# BUS.net
KiCad netlist of a schematic drawn in Altium Designer
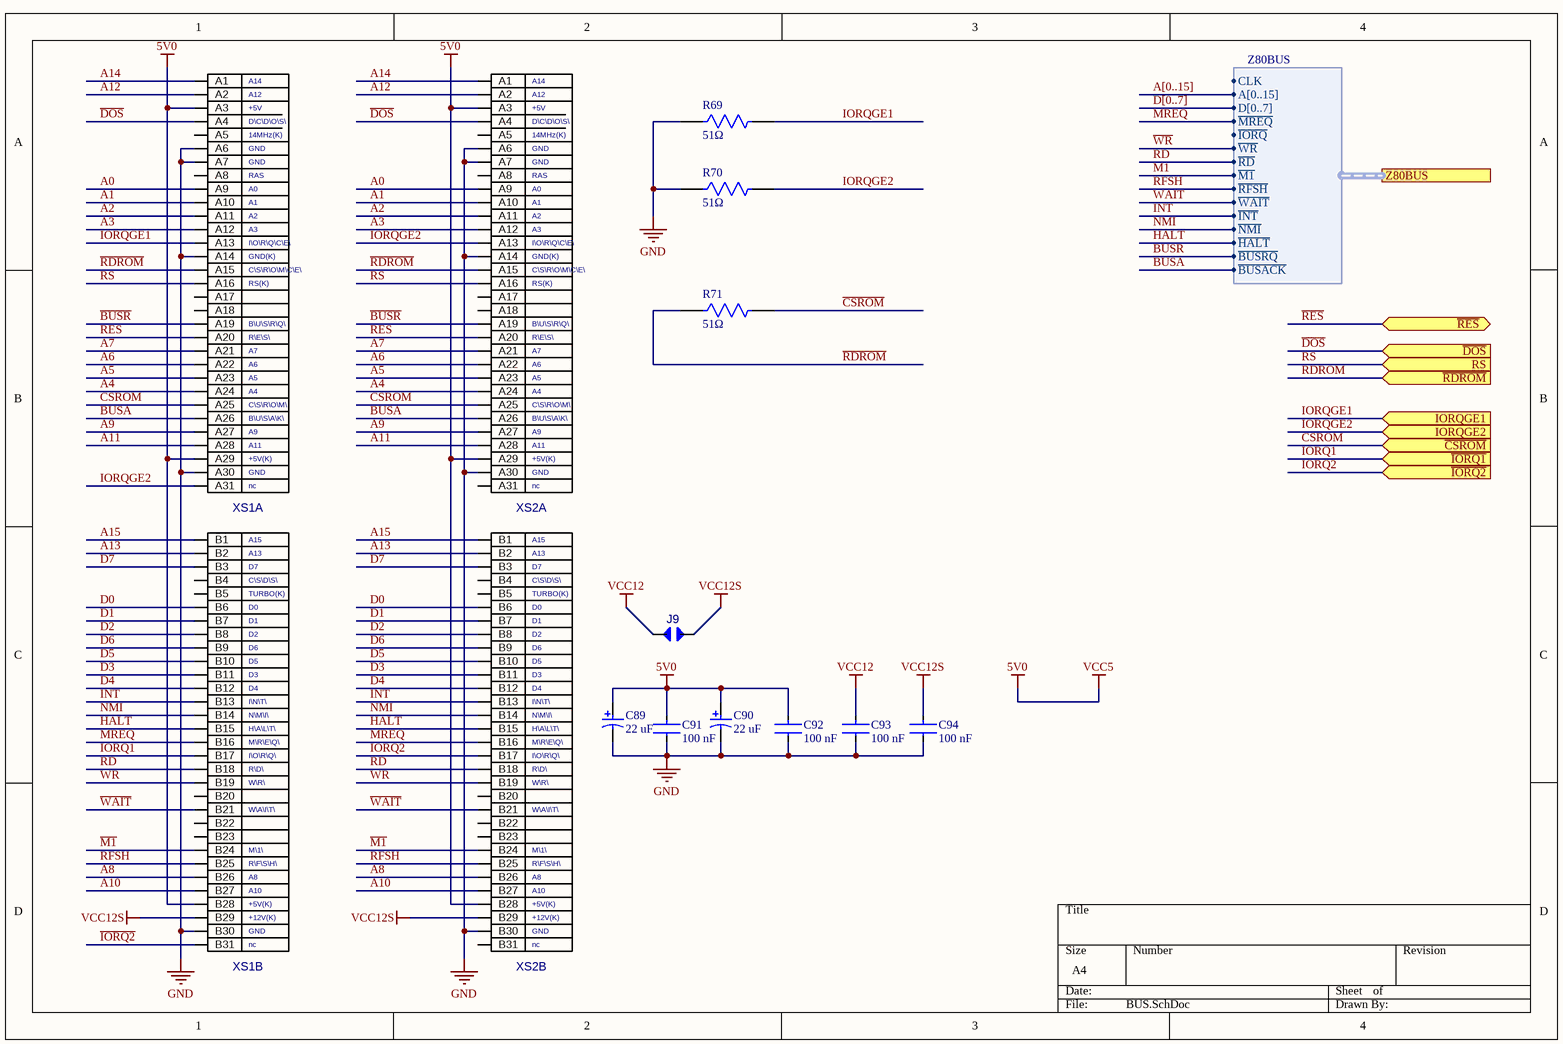
[diagram p0: BUS.SchDoc]

(export (version "E")
  (design (tool "Eeschema 10.0.6"))
  (components
    (comp (ref "C89")
      (value "EC1210-22uF")
      (footprint "AVX-TAJ-B-2_M")
      (description "Standard Tantalum, 22 uF, +/- 10%, 16 V, -55 to 125 degC, 2-Pin SMD (1210), RoHS, Tape and Reel")
      (fields
        (field (name "CAPACITANCE") "22 uF")
        (field (name "MANUFACTURER") "Kyocera AVX")
        (field (name "MANUFACTURER PART NUMBER") "TAJB226K016RNJ")
      )
      (libsource (lib "zxevo") (part "EC1210-22uF"))
    )
    (comp (ref "C90")
      (value "EC1210-22uF")
      (footprint "AVX-TAJ-B-2_M")
      (description "Standard Tantalum, 22 uF, +/- 10%, 16 V, -55 to 125 degC, 2-Pin SMD (1210), RoHS, Tape and Reel")
      (fields
        (field (name "CAPACITANCE") "22 uF")
        (field (name "MANUFACTURER") "Kyocera AVX")
        (field (name "MANUFACTURER PART NUMBER") "TAJB226K016RNJ")
      )
      (libsource (lib "zxevo") (part "EC1210-22uF"))
    )
    (comp (ref "C91")
      (value "CC0805-1.5pF")
      (footprint "CC0805")
      (description "CL21 Series 0805 1.5pF 50V ±0.25pF Tolerance C0G Multilayer Ceramic Chip Capacitor")
      (fields
        (field (name "MANUFACTURER PART NUMBER") "CL21C1R5CBANNNC")
        (field (name "CAPACITANCE") "100 nF")
        (field (name "MANUFACTURER") "Samsung")
      )
      (libsource (lib "zxevo") (part "CC0805"))
    )
    (comp (ref "C92")
      (value "CC0805-1.5pF")
      (footprint "CC0805")
      (description "CL21 Series 0805 1.5pF 50V ±0.25pF Tolerance C0G Multilayer Ceramic Chip Capacitor")
      (fields
        (field (name "MANUFACTURER PART NUMBER") "CL21C1R5CBANNNC")
        (field (name "CAPACITANCE") "100 nF")
        (field (name "MANUFACTURER") "Samsung")
      )
      (libsource (lib "zxevo") (part "CC0805"))
    )
    (comp (ref "C93")
      (value "CC0805-1.5pF")
      (footprint "CC0805")
      (description "CL21 Series 0805 1.5pF 50V ±0.25pF Tolerance C0G Multilayer Ceramic Chip Capacitor")
      (fields
        (field (name "MANUFACTURER PART NUMBER") "CL21C1R5CBANNNC")
        (field (name "CAPACITANCE") "100 nF")
        (field (name "MANUFACTURER") "Samsung")
      )
      (libsource (lib "zxevo") (part "CC0805"))
    )
    (comp (ref "C94")
      (value "CC0805-1.5pF")
      (footprint "CC0805")
      (description "CL21 Series 0805 1.5pF 50V ±0.25pF Tolerance C0G Multilayer Ceramic Chip Capacitor")
      (fields
        (field (name "MANUFACTURER PART NUMBER") "CL21C1R5CBANNNC")
        (field (name "CAPACITANCE") "100 nF")
        (field (name "MANUFACTURER") "Samsung")
      )
      (libsource (lib "zxevo") (part "CC0805"))
    )
    (comp (ref "J9")
      (value "JUMPER")
      (footprint "JUMPER_JUMPER(Primary)")
      (description "HLT->~IP")
      (libsource (lib "zxevo") (part "JUMPER"))
    )
    (comp (ref "R69")
      (value "51Ω")
      (footprint "CR0805")
      (description "51Ω ±0.5% 0.1W 1/10W Chip Resistor 0805 (2012 Metric) Thin Film")
      (fields
        (field (name "MANUFACTURER") "Susumu")
        (field (name "MANUFACTURER PART NUMBER") "RR1220Q-510-D")
      )
      (libsource (lib "zxevo") (part "CR0805"))
    )
    (comp (ref "R70")
      (value "51Ω")
      (footprint "CR0805")
      (description "51Ω ±0.5% 0.1W 1/10W Chip Resistor 0805 (2012 Metric) Thin Film")
      (fields
        (field (name "MANUFACTURER") "Susumu")
        (field (name "MANUFACTURER PART NUMBER") "RR1220Q-510-D")
      )
      (libsource (lib "zxevo") (part "CR0805"))
    )
    (comp (ref "R71")
      (value "51Ω")
      (footprint "CR0805")
      (description "51Ω ±0.5% 0.1W 1/10W Chip Resistor 0805 (2012 Metric) Thin Film")
      (fields
        (field (name "MANUFACTURER") "Susumu")
        (field (name "MANUFACTURER PART NUMBER") "RR1220Q-510-D")
      )
      (libsource (lib "zxevo") (part "CR0805"))
    )
    (comp (ref "XS1")
      (value "ZXSLOT")
      (footprint "SLOT62_ZXSLOT(Primary)")
      (libsource (lib "zxevo") (part "ZXSLOT"))
    )
    (comp (ref "XS2")
      (value "ZXSLOT")
      (footprint "SLOT62_ZXSLOT(Primary)")
      (libsource (lib "zxevo") (part "ZXSLOT"))
    )
  )
  (nets
    (net (code "2") (name "/A0") (class "Default")
      (node (ref "XS1") (pin "A9") (pinfunction "A9_A9") (pintype "passive"))
      (node (ref "XS2") (pin "A9") (pinfunction "A9_A9") (pintype "passive"))
    )
    (net (code "3") (name "/A1") (class "Default")
      (node (ref "XS1") (pin "A10") (pinfunction "A10_A10") (pintype "passive"))
      (node (ref "XS2") (pin "A10") (pinfunction "A10_A10") (pintype "passive"))
    )
    (net (code "4") (name "/A2") (class "Default")
      (node (ref "XS1") (pin "A11") (pinfunction "A11_A11") (pintype "passive"))
      (node (ref "XS2") (pin "A11") (pinfunction "A11_A11") (pintype "passive"))
    )
    (net (code "5") (name "/A3") (class "Default")
      (node (ref "XS1") (pin "A12") (pinfunction "A12_A12") (pintype "passive"))
      (node (ref "XS2") (pin "A12") (pinfunction "A12_A12") (pintype "passive"))
    )
    (net (code "6") (name "/A4") (class "Default")
      (node (ref "XS1") (pin "A24") (pinfunction "A24_A24") (pintype "passive"))
      (node (ref "XS2") (pin "A24") (pinfunction "A24_A24") (pintype "passive"))
    )
    (net (code "7") (name "/A5") (class "Default")
      (node (ref "XS1") (pin "A23") (pinfunction "A23_A23") (pintype "passive"))
      (node (ref "XS2") (pin "A23") (pinfunction "A23_A23") (pintype "passive"))
    )
    (net (code "8") (name "/A6") (class "Default")
      (node (ref "XS1") (pin "A22") (pinfunction "A22_A22") (pintype "passive"))
      (node (ref "XS2") (pin "A22") (pinfunction "A22_A22") (pintype "passive"))
    )
    (net (code "9") (name "/A7") (class "Default")
      (node (ref "XS1") (pin "A21") (pinfunction "A21_A21") (pintype "passive"))
      (node (ref "XS2") (pin "A21") (pinfunction "A21_A21") (pintype "passive"))
    )
    (net (code "10") (name "/A8") (class "Default")
      (node (ref "XS1") (pin "B26") (pinfunction "B26_B26") (pintype "passive"))
      (node (ref "XS2") (pin "B26") (pinfunction "B26_B26") (pintype "passive"))
    )
    (net (code "11") (name "/A9") (class "Default")
      (node (ref "XS1") (pin "A27") (pinfunction "A27_A27") (pintype "passive"))
      (node (ref "XS2") (pin "A27") (pinfunction "A27_A27") (pintype "passive"))
    )
    (net (code "12") (name "/A10") (class "Default")
      (node (ref "XS1") (pin "B27") (pinfunction "B27_B27") (pintype "passive"))
      (node (ref "XS2") (pin "B27") (pinfunction "B27_B27") (pintype "passive"))
    )
    (net (code "13") (name "/A11") (class "Default")
      (node (ref "XS1") (pin "A28") (pinfunction "A28_A28") (pintype "passive"))
      (node (ref "XS2") (pin "A28") (pinfunction "A28_A28") (pintype "passive"))
    )
    (net (code "14") (name "/A12") (class "Default")
      (node (ref "XS1") (pin "A2") (pinfunction "A2_A2") (pintype "passive"))
      (node (ref "XS2") (pin "A2") (pinfunction "A2_A2") (pintype "passive"))
    )
    (net (code "15") (name "/A13") (class "Default")
      (node (ref "XS1") (pin "B2") (pinfunction "B2_B2") (pintype "passive"))
      (node (ref "XS2") (pin "B2") (pinfunction "B2_B2") (pintype "passive"))
    )
    (net (code "16") (name "/A14") (class "Default")
      (node (ref "XS1") (pin "A1") (pinfunction "A1_A1") (pintype "passive"))
      (node (ref "XS2") (pin "A1") (pinfunction "A1_A1") (pintype "passive"))
    )
    (net (code "17") (name "/A15") (class "Default")
      (node (ref "XS1") (pin "B1") (pinfunction "B1_B1") (pintype "passive"))
      (node (ref "XS2") (pin "B1") (pinfunction "B1_B1") (pintype "passive"))
    )
    (net (code "19") (name "/D0") (class "Default")
      (node (ref "XS1") (pin "B6") (pinfunction "B6_B6") (pintype "passive"))
      (node (ref "XS2") (pin "B6") (pinfunction "B6_B6") (pintype "passive"))
    )
    (net (code "20") (name "/D1") (class "Default")
      (node (ref "XS1") (pin "B7") (pinfunction "B7_B7") (pintype "passive"))
      (node (ref "XS2") (pin "B7") (pinfunction "B7_B7") (pintype "passive"))
    )
    (net (code "21") (name "/D2") (class "Default")
      (node (ref "XS1") (pin "B8") (pinfunction "B8_B8") (pintype "passive"))
      (node (ref "XS2") (pin "B8") (pinfunction "B8_B8") (pintype "passive"))
    )
    (net (code "22") (name "/D3") (class "Default")
      (node (ref "XS1") (pin "B11") (pinfunction "B11_B11") (pintype "passive"))
      (node (ref "XS2") (pin "B11") (pinfunction "B11_B11") (pintype "passive"))
    )
    (net (code "23") (name "/D4") (class "Default")
      (node (ref "XS1") (pin "B12") (pinfunction "B12_B12") (pintype "passive"))
      (node (ref "XS2") (pin "B12") (pinfunction "B12_B12") (pintype "passive"))
    )
    (net (code "24") (name "/D5") (class "Default")
      (node (ref "XS1") (pin "B10") (pinfunction "B10_B10") (pintype "passive"))
      (node (ref "XS2") (pin "B10") (pinfunction "B10_B10") (pintype "passive"))
    )
    (net (code "25") (name "/D6") (class "Default")
      (node (ref "XS1") (pin "B9") (pinfunction "B9_B9") (pintype "passive"))
      (node (ref "XS2") (pin "B9") (pinfunction "B9_B9") (pintype "passive"))
    )
    (net (code "26") (name "/D7") (class "Default")
      (node (ref "XS1") (pin "B3") (pinfunction "B3_B3") (pintype "passive"))
      (node (ref "XS2") (pin "B3") (pinfunction "B3_B3") (pintype "passive"))
    )
    (net (code "28") (name "/IORQGE1") (class "Default")
      (node (ref "R69") (pin "2") (pinfunction "2_2") (pintype "passive"))
      (node (ref "XS1") (pin "A13") (pinfunction "A13_A13") (pintype "passive"))
    )
    (net (code "29") (name "/IORQGE2") (class "Default")
      (node (ref "R70") (pin "2") (pinfunction "2_2") (pintype "passive"))
      (node (ref "XS1") (pin "A31") (pinfunction "A31_A31") (pintype "passive"))
      (node (ref "XS2") (pin "A13") (pinfunction "A13_A13") (pintype "passive"))
    )
    (net (code "30") (name "/RS") (class "Default")
      (node (ref "XS1") (pin "A16") (pinfunction "A16_A16") (pintype "passive"))
      (node (ref "XS2") (pin "A16") (pinfunction "A16_A16") (pintype "passive"))
    )
    (net (code "32") (name "/~{BUSA}") (class "Default")
      (node (ref "XS1") (pin "A26") (pinfunction "A26_A26") (pintype "passive"))
      (node (ref "XS2") (pin "A26") (pinfunction "A26_A26") (pintype "passive"))
    )
    (net (code "33") (name "/~{BUSR}") (class "Default")
      (node (ref "XS1") (pin "A19") (pinfunction "A19_A19") (pintype "passive"))
      (node (ref "XS2") (pin "A19") (pinfunction "A19_A19") (pintype "passive"))
    )
    (net (code "34") (name "/~{CSROM}") (class "Default")
      (node (ref "R71") (pin "2") (pinfunction "2_2") (pintype "passive"))
      (node (ref "XS1") (pin "A25") (pinfunction "A25_A25") (pintype "passive"))
      (node (ref "XS2") (pin "A25") (pinfunction "A25_A25") (pintype "passive"))
    )
    (net (code "35") (name "/~{DOS}") (class "Default")
      (node (ref "XS1") (pin "A4") (pinfunction "A4_A4") (pintype "passive"))
      (node (ref "XS2") (pin "A4") (pinfunction "A4_A4") (pintype "passive"))
    )
    (net (code "36") (name "/~{HALT}") (class "Default")
      (node (ref "XS1") (pin "B15") (pinfunction "B15_B15") (pintype "passive"))
      (node (ref "XS2") (pin "B15") (pinfunction "B15_B15") (pintype "passive"))
    )
    (net (code "37") (name "/~{INT}") (class "Default")
      (node (ref "XS1") (pin "B13") (pinfunction "B13_B13") (pintype "passive"))
      (node (ref "XS2") (pin "B13") (pinfunction "B13_B13") (pintype "passive"))
    )
    (net (code "38") (name "/~{IORQ1}") (class "Default")
      (node (ref "XS1") (pin "B17") (pinfunction "B17_B17") (pintype "passive"))
    )
    (net (code "39") (name "/~{IORQ2}") (class "Default")
      (node (ref "XS1") (pin "B31") (pinfunction "B31_B31") (pintype "passive"))
      (node (ref "XS2") (pin "B17") (pinfunction "B17_B17") (pintype "passive"))
    )
    (net (code "40") (name "/~{M1}") (class "Default")
      (node (ref "XS1") (pin "B24") (pinfunction "B24_B24") (pintype "passive"))
      (node (ref "XS2") (pin "B24") (pinfunction "B24_B24") (pintype "passive"))
    )
    (net (code "41") (name "/~{MREQ}") (class "Default")
      (node (ref "XS1") (pin "B16") (pinfunction "B16_B16") (pintype "passive"))
      (node (ref "XS2") (pin "B16") (pinfunction "B16_B16") (pintype "passive"))
    )
    (net (code "42") (name "/~{NMI}") (class "Default")
      (node (ref "XS1") (pin "B14") (pinfunction "B14_B14") (pintype "passive"))
      (node (ref "XS2") (pin "B14") (pinfunction "B14_B14") (pintype "passive"))
    )
    (net (code "43") (name "/~{RDROM}") (class "Default")
      (node (ref "R71") (pin "1") (pinfunction "1_1") (pintype "passive"))
      (node (ref "XS1") (pin "A15") (pinfunction "A15_A15") (pintype "passive"))
      (node (ref "XS2") (pin "A15") (pinfunction "A15_A15") (pintype "passive"))
    )
    (net (code "44") (name "/~{RD}") (class "Default")
      (node (ref "XS1") (pin "B18") (pinfunction "B18_B18") (pintype "passive"))
      (node (ref "XS2") (pin "B18") (pinfunction "B18_B18") (pintype "passive"))
    )
    (net (code "45") (name "/~{RES}") (class "Default")
      (node (ref "XS1") (pin "A20") (pinfunction "A20_A20") (pintype "passive"))
      (node (ref "XS2") (pin "A20") (pinfunction "A20_A20") (pintype "passive"))
    )
    (net (code "46") (name "/~{RFSH}") (class "Default")
      (node (ref "XS1") (pin "B25") (pinfunction "B25_B25") (pintype "passive"))
      (node (ref "XS2") (pin "B25") (pinfunction "B25_B25") (pintype "passive"))
    )
    (net (code "47") (name "/~{WAIT}") (class "Default")
      (node (ref "XS1") (pin "B21") (pinfunction "B21_B21") (pintype "passive"))
      (node (ref "XS2") (pin "B21") (pinfunction "B21_B21") (pintype "passive"))
    )
    (net (code "48") (name "/~{WR}") (class "Default")
      (node (ref "XS1") (pin "B19") (pinfunction "B19_B19") (pintype "passive"))
      (node (ref "XS2") (pin "B19") (pinfunction "B19_B19") (pintype "passive"))
    )
    (net (code "49") (name "5V0") (class "Default")
      (node (ref "C89") (pin "1") (pinfunction "1_1") (pintype "passive"))
      (node (ref "C90") (pin "1") (pinfunction "1_1") (pintype "passive"))
      (node (ref "C91") (pin "1") (pinfunction "1_1") (pintype "passive"))
      (node (ref "C92") (pin "1") (pinfunction "1_1") (pintype "passive"))
      (node (ref "XS1") (pin "A29") (pinfunction "A29_A29") (pintype "passive"))
      (node (ref "XS1") (pin "A3") (pinfunction "A3_A3") (pintype "passive"))
      (node (ref "XS1") (pin "B28") (pinfunction "B28_B28") (pintype "passive"))
      (node (ref "XS2") (pin "A29") (pinfunction "A29_A29") (pintype "passive"))
      (node (ref "XS2") (pin "A3") (pinfunction "A3_A3") (pintype "passive"))
      (node (ref "XS2") (pin "B28") (pinfunction "B28_B28") (pintype "passive"))
    )
    (net (code "50") (name "GND") (class "Default")
      (node (ref "C89") (pin "2") (pinfunction "2_2") (pintype "passive"))
      (node (ref "C90") (pin "2") (pinfunction "2_2") (pintype "passive"))
      (node (ref "C91") (pin "2") (pinfunction "2_2") (pintype "passive"))
      (node (ref "C92") (pin "2") (pinfunction "2_2") (pintype "passive"))
      (node (ref "C93") (pin "2") (pinfunction "2_2") (pintype "passive"))
      (node (ref "C94") (pin "2") (pinfunction "2_2") (pintype "passive"))
      (node (ref "R69") (pin "1") (pinfunction "1_1") (pintype "passive"))
      (node (ref "R70") (pin "1") (pinfunction "1_1") (pintype "passive"))
      (node (ref "XS1") (pin "A14") (pinfunction "A14_A14") (pintype "passive"))
      (node (ref "XS1") (pin "A30") (pinfunction "A30_A30") (pintype "passive"))
      (node (ref "XS1") (pin "A6") (pinfunction "A6_A6") (pintype "passive"))
      (node (ref "XS1") (pin "A7") (pinfunction "A7_A7") (pintype "passive"))
      (node (ref "XS1") (pin "B30") (pinfunction "B30_B30") (pintype "passive"))
      (node (ref "XS2") (pin "A14") (pinfunction "A14_A14") (pintype "passive"))
      (node (ref "XS2") (pin "A30") (pinfunction "A30_A30") (pintype "passive"))
      (node (ref "XS2") (pin "A6") (pinfunction "A6_A6") (pintype "passive"))
      (node (ref "XS2") (pin "A7") (pinfunction "A7_A7") (pintype "passive"))
      (node (ref "XS2") (pin "B30") (pinfunction "B30_B30") (pintype "passive"))
    )
    (net (code "51") (name "VCC12") (class "Default")
      (node (ref "C93") (pin "1") (pinfunction "1_1") (pintype "passive"))
      (node (ref "J9") (pin "0") (pinfunction "1_0") (pintype "passive"))
    )
    (net (code "52") (name "VCC12S") (class "Default")
      (node (ref "C94") (pin "1") (pinfunction "1_1") (pintype "passive"))
      (node (ref "J9") (pin "1") (pinfunction "2_1") (pintype "passive"))
      (node (ref "XS1") (pin "B29") (pinfunction "B29_B29") (pintype "passive"))
      (node (ref "XS2") (pin "B29") (pinfunction "B29_B29") (pintype "passive"))
    )
    (net (code "53") (name "unconnected-(XS1-PadA5)") (class "Default")
      (node (ref "XS1") (pin "A5") (pinfunction "A5_A5") (pintype "passive"))
    )
    (net (code "54") (name "unconnected-(XS1-PadA8)") (class "Default")
      (node (ref "XS1") (pin "A8") (pinfunction "A8_A8") (pintype "passive"))
    )
    (net (code "55") (name "unconnected-(XS1-PadA17)") (class "Default")
      (node (ref "XS1") (pin "A17") (pinfunction "A17_A17") (pintype "passive"))
    )
    (net (code "56") (name "unconnected-(XS1-PadA18)") (class "Default")
      (node (ref "XS1") (pin "A18") (pinfunction "A18_A18") (pintype "passive"))
    )
    (net (code "57") (name "unconnected-(XS1-PadB4)") (class "Default")
      (node (ref "XS1") (pin "B4") (pinfunction "B4_B4") (pintype "passive"))
    )
    (net (code "58") (name "unconnected-(XS1-PadB5)") (class "Default")
      (node (ref "XS1") (pin "B5") (pinfunction "B5_B5") (pintype "passive"))
    )
    (net (code "59") (name "unconnected-(XS1-PadB20)") (class "Default")
      (node (ref "XS1") (pin "B20") (pinfunction "B20_B20") (pintype "passive"))
    )
    (net (code "60") (name "unconnected-(XS1-PadB22)") (class "Default")
      (node (ref "XS1") (pin "B22") (pinfunction "B22_B22") (pintype "passive"))
    )
    (net (code "61") (name "unconnected-(XS1-PadB23)") (class "Default")
      (node (ref "XS1") (pin "B23") (pinfunction "B23_B23") (pintype "passive"))
    )
    (net (code "62") (name "unconnected-(XS2-PadA5)") (class "Default")
      (node (ref "XS2") (pin "A5") (pinfunction "A5_A5") (pintype "passive"))
    )
    (net (code "63") (name "unconnected-(XS2-PadA8)") (class "Default")
      (node (ref "XS2") (pin "A8") (pinfunction "A8_A8") (pintype "passive"))
    )
    (net (code "64") (name "unconnected-(XS2-PadA17)") (class "Default")
      (node (ref "XS2") (pin "A17") (pinfunction "A17_A17") (pintype "passive"))
    )
    (net (code "65") (name "unconnected-(XS2-PadA18)") (class "Default")
      (node (ref "XS2") (pin "A18") (pinfunction "A18_A18") (pintype "passive"))
    )
    (net (code "66") (name "unconnected-(XS2-PadA31)") (class "Default")
      (node (ref "XS2") (pin "A31") (pinfunction "A31_A31") (pintype "passive"))
    )
    (net (code "67") (name "unconnected-(XS2-PadB4)") (class "Default")
      (node (ref "XS2") (pin "B4") (pinfunction "B4_B4") (pintype "passive"))
    )
    (net (code "68") (name "unconnected-(XS2-PadB5)") (class "Default")
      (node (ref "XS2") (pin "B5") (pinfunction "B5_B5") (pintype "passive"))
    )
    (net (code "69") (name "unconnected-(XS2-PadB20)") (class "Default")
      (node (ref "XS2") (pin "B20") (pinfunction "B20_B20") (pintype "passive"))
    )
    (net (code "70") (name "unconnected-(XS2-PadB22)") (class "Default")
      (node (ref "XS2") (pin "B22") (pinfunction "B22_B22") (pintype "passive"))
    )
    (net (code "71") (name "unconnected-(XS2-PadB23)") (class "Default")
      (node (ref "XS2") (pin "B23") (pinfunction "B23_B23") (pintype "passive"))
    )
    (net (code "72") (name "unconnected-(XS2-PadB31)") (class "Default")
      (node (ref "XS2") (pin "B31") (pinfunction "B31_B31") (pintype "passive"))
    )
  )
)
